# MD2017_Ctrl.net
KiCad netlist of a schematic drawn in EAGLE
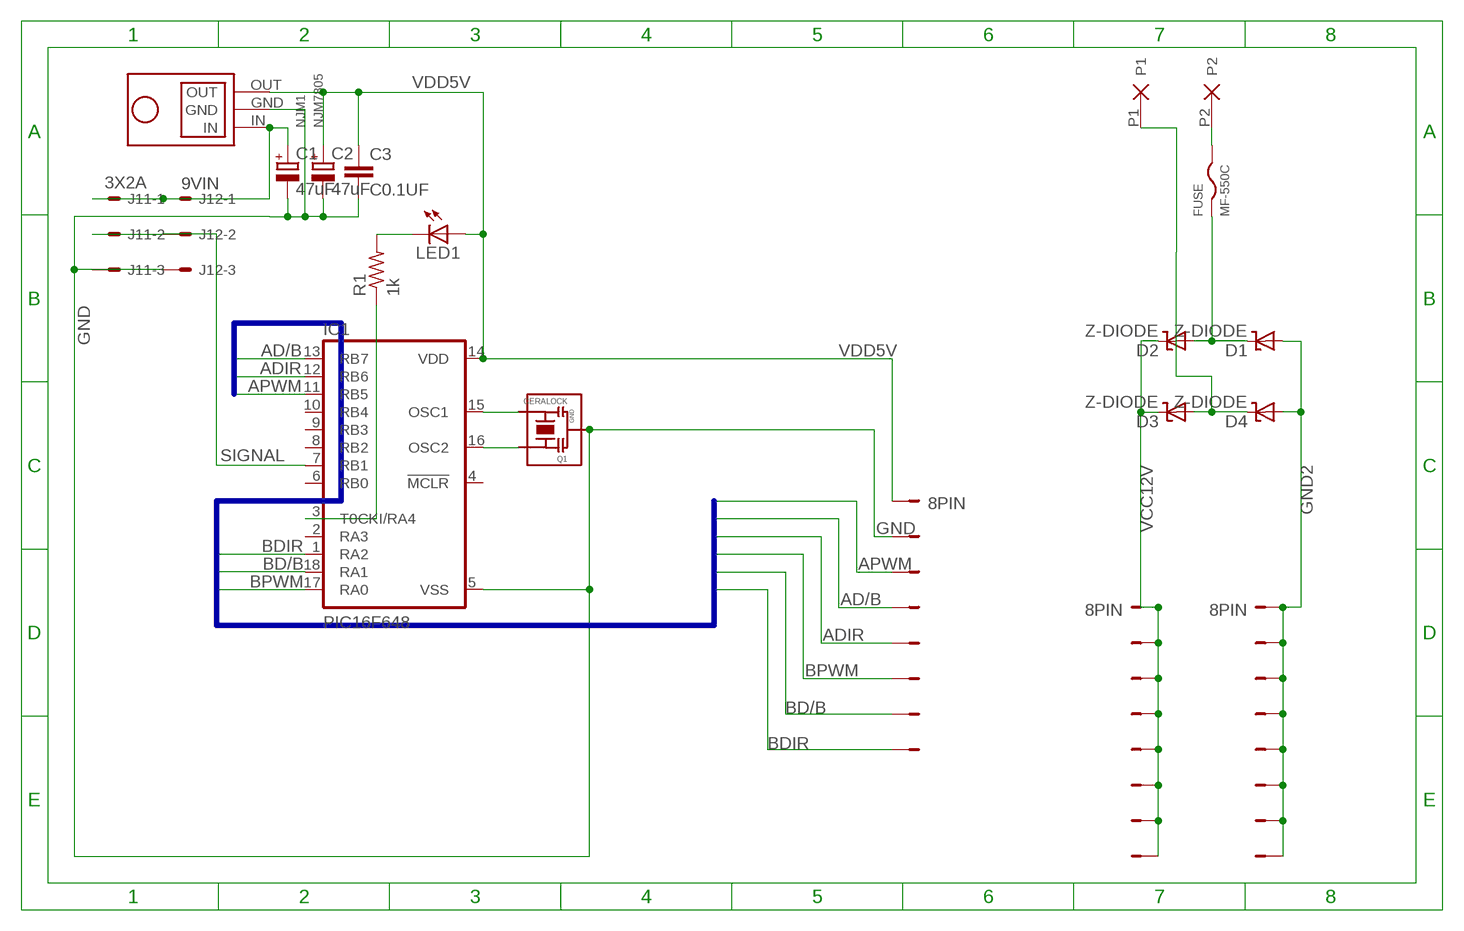
[diagram p0: schematic, sheet 1]

(export (version "E")
  (design (tool "Eeschema 10.0.6"))
  (components
    (comp (ref "C1")
      (value "47uF")
      (footprint "eagle-import:E2-5")
      (libsource (lib "eagle-import") (part "CPOL-EU2-5MM"))
    )
    (comp (ref "C2")
      (value "47uF")
      (footprint "eagle-import:E2-5")
      (libsource (lib "eagle-import") (part "CPOL-EU2-5MM"))
    )
    (comp (ref "C3")
      (value "C0.1UF")
      (footprint "eagle-import:C0.1UF")
      (libsource (lib "eagle-import") (part "C0.1UF"))
    )
    (comp (ref "D1")
      (value "Z-DIODE")
      (footprint "eagle-import:DO201-15")
      (libsource (lib "eagle-import") (part "Z-DIODE"))
    )
    (comp (ref "D2")
      (value "Z-DIODE")
      (footprint "eagle-import:DO201-15")
      (libsource (lib "eagle-import") (part "Z-DIODE"))
    )
    (comp (ref "D3")
      (value "Z-DIODE")
      (footprint "eagle-import:DO201-15")
      (libsource (lib "eagle-import") (part "Z-DIODE"))
    )
    (comp (ref "D4")
      (value "Z-DIODE")
      (footprint "eagle-import:DO201-15")
      (libsource (lib "eagle-import") (part "Z-DIODE"))
    )
    (comp (ref "FUSE")
      (value "MF-550C")
      (footprint "eagle-import:MF550C")
      (libsource (lib "eagle-import") (part "MF-550C"))
    )
    (comp (ref "IC1")
      (value "PIC16F648")
      (footprint "eagle-import:DIL18")
      (libsource (lib "eagle-import") (part "PIC16F648"))
    )
    (comp (ref "J1")
      (value "3X2A")
      (footprint "eagle-import:37206-62A3-003")
      (libsource (lib "eagle-import") (part "3X2A"))
    )
    (comp (ref "LED1")
      (value "LED5MM")
      (footprint "eagle-import:LED5MM")
      (libsource (lib "eagle-import") (part "LED5MM"))
    )
    (comp (ref "NJM1")
      (value "NJM7805")
      (footprint "eagle-import:NJM7805")
      (libsource (lib "eagle-import") (part "NJM7805"))
    )
    (comp (ref "POWERNPORT")
      (value "8PIN")
      (footprint "eagle-import:FH105-1X8SG")
      (libsource (lib "eagle-import") (part "8PIN"))
    )
    (comp (ref "POWERPPORT")
      (value "8PIN")
      (footprint "eagle-import:FH105-1X8SG")
      (libsource (lib "eagle-import") (part "8PIN"))
    )
    (comp (ref "Q1")
      (value "CERALOCK")
      (footprint "eagle-import:CERALOCK")
      (libsource (lib "eagle-import") (part "CERALOCK"))
    )
    (comp (ref "R1")
      (value "1k")
      (footprint "eagle-import:R3216W")
      (libsource (lib "eagle-import") (part "R-US_R3216W"))
    )
    (comp (ref "SIGNALPORT")
      (value "8PIN")
      (footprint "eagle-import:FH105-1X8SG")
      (libsource (lib "eagle-import") (part "8PIN"))
    )
    (comp (ref "U$2") (value "2P") (footprint "eagle-import:2P") (libsource (lib "eagle-import") (part "2P")))
  )
  (nets
    (net (code "1") (name "/9VIN") (class "Default")
      (node (ref "C1") (pin "+") (pinfunction "+_+") (pintype "passive"))
      (node (ref "J1") (pin "1-1") (pinfunction "S_1-1") (pintype "passive"))
      (node (ref "J1") (pin "2-1") (pinfunction "S_2-1") (pintype "passive"))
      (node (ref "NJM1") (pin "IN") (pinfunction "IN_IN") (pintype "bidirectional"))
    )
    (net (code "2") (name "/ADIR") (class "Default")
      (node (ref "IC1") (pin "12") (pinfunction "RB6_12") (pintype "bidirectional"))
      (node (ref "SIGNALPORT") (pin "5") (pinfunction "P$1_5") (pintype "passive"))
    )
    (net (code "3") (name "/AD{slash}B") (class "Default")
      (node (ref "IC1") (pin "13") (pinfunction "RB7_13") (pintype "bidirectional"))
      (node (ref "SIGNALPORT") (pin "4") (pinfunction "P$1_4") (pintype "passive"))
    )
    (net (code "4") (name "/APWM") (class "Default")
      (node (ref "IC1") (pin "11") (pinfunction "RB5_11") (pintype "bidirectional"))
      (node (ref "SIGNALPORT") (pin "3") (pinfunction "P$1_3") (pintype "passive"))
    )
    (net (code "5") (name "/BDIR") (class "Default")
      (node (ref "IC1") (pin "1") (pinfunction "RA2_1") (pintype "bidirectional"))
      (node (ref "SIGNALPORT") (pin "8") (pinfunction "P$1_8") (pintype "passive"))
    )
    (net (code "6") (name "/BD{slash}B") (class "Default")
      (node (ref "IC1") (pin "18") (pinfunction "RA1_18") (pintype "bidirectional"))
      (node (ref "SIGNALPORT") (pin "7") (pinfunction "P$1_7") (pintype "passive"))
    )
    (net (code "7") (name "/BPWM") (class "Default")
      (node (ref "IC1") (pin "17") (pinfunction "RA0_17") (pintype "bidirectional"))
      (node (ref "SIGNALPORT") (pin "6") (pinfunction "P$1_6") (pintype "passive"))
    )
    (net (code "8") (name "/GND") (class "Default")
      (node (ref "C1") (pin "-") (pinfunction "-_-") (pintype "passive"))
      (node (ref "C2") (pin "-") (pinfunction "-_-") (pintype "passive"))
      (node (ref "C3") (pin "2") (pinfunction "2_2") (pintype "passive"))
      (node (ref "IC1") (pin "5") (pinfunction "VSS_5") (pintype "power_in"))
      (node (ref "J1") (pin "1-3") (pinfunction "S_1-3") (pintype "passive"))
      (node (ref "J1") (pin "2-3") (pinfunction "S_2-3") (pintype "passive"))
      (node (ref "NJM1") (pin "GND") (pinfunction "GND_GND") (pintype "bidirectional"))
      (node (ref "Q1") (pin "P$2") (pinfunction "P$2_P$2") (pintype "passive"))
      (node (ref "SIGNALPORT") (pin "2") (pinfunction "P$1_2") (pintype "passive"))
    )
    (net (code "9") (name "/GND2") (class "Default")
      (node (ref "D1") (pin "A") (pinfunction "A_A") (pintype "passive"))
      (node (ref "D4") (pin "A") (pinfunction "A_A") (pintype "passive"))
      (node (ref "POWERNPORT") (pin "1") (pinfunction "P$1_1") (pintype "passive"))
      (node (ref "POWERNPORT") (pin "2") (pinfunction "P$1_2") (pintype "passive"))
      (node (ref "POWERNPORT") (pin "3") (pinfunction "P$1_3") (pintype "passive"))
      (node (ref "POWERNPORT") (pin "4") (pinfunction "P$1_4") (pintype "passive"))
      (node (ref "POWERNPORT") (pin "5") (pinfunction "P$1_5") (pintype "passive"))
      (node (ref "POWERNPORT") (pin "6") (pinfunction "P$1_6") (pintype "passive"))
      (node (ref "POWERNPORT") (pin "7") (pinfunction "P$1_7") (pintype "passive"))
      (node (ref "POWERNPORT") (pin "8") (pinfunction "P$1_8") (pintype "passive"))
    )
    (net (code "10") (name "/SIGNAL") (class "Default")
      (node (ref "IC1") (pin "7") (pinfunction "RB1_7") (pintype "bidirectional"))
      (node (ref "J1") (pin "1-2") (pinfunction "S_1-2") (pintype "passive"))
      (node (ref "J1") (pin "2-2") (pinfunction "S_2-2") (pintype "passive"))
    )
    (net (code "11") (name "/VCC12V") (class "Default")
      (node (ref "D2") (pin "C") (pinfunction "C_C") (pintype "passive"))
      (node (ref "D3") (pin "C") (pinfunction "C_C") (pintype "passive"))
      (node (ref "POWERPPORT") (pin "1") (pinfunction "P$1_1") (pintype "passive"))
      (node (ref "POWERPPORT") (pin "2") (pinfunction "P$1_2") (pintype "passive"))
      (node (ref "POWERPPORT") (pin "3") (pinfunction "P$1_3") (pintype "passive"))
      (node (ref "POWERPPORT") (pin "4") (pinfunction "P$1_4") (pintype "passive"))
      (node (ref "POWERPPORT") (pin "5") (pinfunction "P$1_5") (pintype "passive"))
      (node (ref "POWERPPORT") (pin "6") (pinfunction "P$1_6") (pintype "passive"))
      (node (ref "POWERPPORT") (pin "7") (pinfunction "P$1_7") (pintype "passive"))
      (node (ref "POWERPPORT") (pin "8") (pinfunction "P$1_8") (pintype "passive"))
    )
    (net (code "12") (name "/VDD5V") (class "Default")
      (node (ref "C2") (pin "+") (pinfunction "+_+") (pintype "passive"))
      (node (ref "C3") (pin "1") (pinfunction "1_1") (pintype "passive"))
      (node (ref "IC1") (pin "14") (pinfunction "VDD_14") (pintype "power_in"))
      (node (ref "LED1") (pin "A") (pinfunction "A_A") (pintype "passive"))
      (node (ref "NJM1") (pin "OUT") (pinfunction "OUT_OUT") (pintype "bidirectional"))
      (node (ref "SIGNALPORT") (pin "1") (pinfunction "P$1_1") (pintype "passive"))
    )
    (net (code "13") (name "Net-(D1-PadC)") (class "Default")
      (node (ref "D1") (pin "C") (pinfunction "C_C") (pintype "passive"))
      (node (ref "D2") (pin "A") (pinfunction "A_A") (pintype "passive"))
      (node (ref "FUSE") (pin "PA") (pinfunction "PA_PA") (pintype "passive"))
    )
    (net (code "14") (name "Net-(D3-PadA)") (class "Default")
      (node (ref "D3") (pin "A") (pinfunction "A_A") (pintype "passive"))
      (node (ref "D4") (pin "C") (pinfunction "C_C") (pintype "passive"))
      (node (ref "U$2") (pin "P1") (pinfunction "P1_P1") (pintype "bidirectional"))
    )
    (net (code "15") (name "Net-(FUSE-PadPB)") (class "Default")
      (node (ref "FUSE") (pin "PB") (pinfunction "PB_PB") (pintype "passive"))
      (node (ref "U$2") (pin "P2") (pinfunction "P2_P2") (pintype "bidirectional"))
    )
    (net (code "16") (name "Net-(IC1-OSC1)") (class "Default")
      (node (ref "IC1") (pin "15") (pinfunction "OSC1_15") (pintype "input"))
      (node (ref "Q1") (pin "P$3") (pinfunction "P$3_P$3") (pintype "passive"))
    )
    (net (code "17") (name "Net-(IC1-OSC2)") (class "Default")
      (node (ref "IC1") (pin "16") (pinfunction "OSC2_16") (pintype "output"))
      (node (ref "Q1") (pin "P$1") (pinfunction "P$1_P$1") (pintype "passive"))
    )
    (net (code "18") (name "Net-(IC1-T0CKI{slash}RA4)") (class "Default")
      (node (ref "IC1") (pin "3") (pinfunction "T0CKI/RA4_3") (pintype "bidirectional"))
      (node (ref "R1") (pin "1") (pinfunction "1_1") (pintype "passive"))
    )
    (net (code "19") (name "Net-(LED1-C)") (class "Default")
      (node (ref "LED1") (pin "K") (pinfunction "C_K") (pintype "passive"))
      (node (ref "R1") (pin "2") (pinfunction "2_2") (pintype "passive"))
    )
    (net (code "20") (name "unconnected-(IC1-RA3-Pad2)") (class "Default")
      (node (ref "IC1") (pin "2") (pinfunction "RA3_2") (pintype "bidirectional"))
    )
    (net (code "21") (name "unconnected-(IC1-RB0-Pad6)") (class "Default")
      (node (ref "IC1") (pin "6") (pinfunction "RB0_6") (pintype "bidirectional"))
    )
    (net (code "22") (name "unconnected-(IC1-RB2-Pad8)") (class "Default")
      (node (ref "IC1") (pin "8") (pinfunction "RB2_8") (pintype "bidirectional"))
    )
    (net (code "23") (name "unconnected-(IC1-RB3-Pad9)") (class "Default")
      (node (ref "IC1") (pin "9") (pinfunction "RB3_9") (pintype "bidirectional"))
    )
    (net (code "24") (name "unconnected-(IC1-RB4-Pad10)") (class "Default")
      (node (ref "IC1") (pin "10") (pinfunction "RB4_10") (pintype "bidirectional"))
    )
    (net (code "25") (name "unconnected-(IC1-~{MCLR}-Pad4)") (class "Default")
      (node (ref "IC1") (pin "4") (pinfunction "~{MCLR}_4") (pintype "input"))
    )
  )
)
